# air.net
KiCad netlist of a schematic drawn in EAGLE
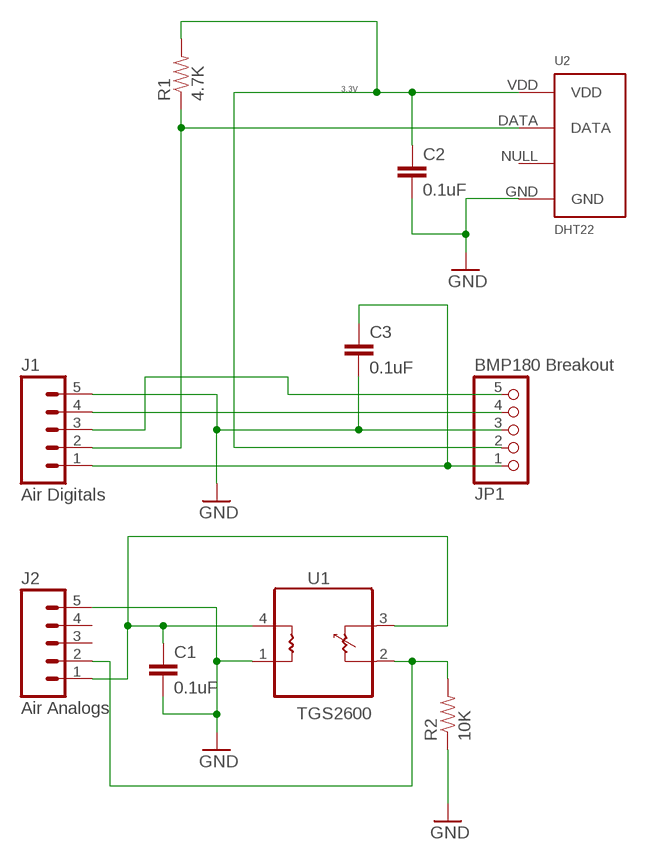
[diagram p0: schematic, sheet 1]

(export (version "E")
  (design (tool "Eeschema 10.0.6"))
  (components
    (comp (ref "C1")
      (value "0.1uF")
      (footprint "eagle-import:CAP-PTH-SMALL")
      (libsource (lib "eagle-import") (part "CAPPTH"))
    )
    (comp (ref "C2")
      (value "0.1uF")
      (footprint "eagle-import:CAP-PTH-SMALL")
      (libsource (lib "eagle-import") (part "CAPPTH"))
    )
    (comp (ref "C3")
      (value "0.1uF")
      (footprint "eagle-import:CAP-PTH-SMALL")
      (libsource (lib "eagle-import") (part "CAPPTH"))
    )
    (comp (ref "J1")
      (value "Air Digitals")
      (footprint "eagle-import:SCREWTERMINAL-3.5MM-5")
      (libsource (lib "eagle-import") (part "M05SCREW"))
    )
    (comp (ref "J2")
      (value "Air Analogs")
      (footprint "eagle-import:SCREWTERMINAL-3.5MM-5")
      (libsource (lib "eagle-import") (part "M05SCREW"))
    )
    (comp (ref "JP1")
      (value "BMP180 Breakout")
      (footprint "eagle-import:1X05_ROUND_70")
      (libsource (lib "eagle-import") (part "HEADER-1X570MIL"))
    )
    (comp (ref "R1")
      (value "4.7K")
      (footprint "eagle-import:AXIAL-0.4")
      (libsource (lib "eagle-import") (part "RESISTORPTH-1/4W"))
    )
    (comp (ref "R2")
      (value "10K")
      (footprint "eagle-import:AXIAL-0.4")
      (libsource (lib "eagle-import") (part "RESISTORPTH-1/4W"))
    )
    (comp (ref "U1")
      (value "TGS2600")
      (footprint "eagle-import:TO5_AIRQ")
      (libsource (lib "eagle-import") (part "TGN2600"))
    )
    (comp (ref "U2")
      (value "DHT22")
      (footprint "eagle-import:AM2302")
      (libsource (lib "eagle-import") (part "RHT03_DHT-22_AM2302WIRED"))
    )
  )
  (nets
    (net (code "1") (name "/3.3V") (class "Default")
      (node (ref "C2") (pin "1") (pinfunction "1_1") (pintype "passive"))
      (node (ref "JP1") (pin "2") (pinfunction "2_2") (pintype "passive"))
      (node (ref "R1") (pin "P$2") (pinfunction "2_P$2") (pintype "passive"))
      (node (ref "U2") (pin "VDD") (pinfunction "VDD_VDD") (pintype "power_in"))
    )
    (net (code "2") (name "GND") (class "Default")
      (node (ref "C1") (pin "2") (pinfunction "2_2") (pintype "passive"))
      (node (ref "C2") (pin "2") (pinfunction "2_2") (pintype "passive"))
      (node (ref "C3") (pin "2") (pinfunction "2_2") (pintype "passive"))
      (node (ref "J1") (pin "5") (pinfunction "5_5") (pintype "passive"))
      (node (ref "J2") (pin "5") (pinfunction "5_5") (pintype "passive"))
      (node (ref "JP1") (pin "3") (pinfunction "3_3") (pintype "passive"))
      (node (ref "R2") (pin "P$1") (pinfunction "1_P$1") (pintype "passive"))
      (node (ref "U1") (pin "1") (pinfunction "1_1") (pintype "passive"))
      (node (ref "U2") (pin "GND") (pinfunction "GND_GND") (pintype "power_in"))
    )
    (net (code "3") (name "Net-(C1-Pad1)") (class "Default")
      (node (ref "C1") (pin "1") (pinfunction "1_1") (pintype "passive"))
      (node (ref "J2") (pin "1") (pinfunction "1_1") (pintype "passive"))
      (node (ref "U1") (pin "3") (pinfunction "3_3") (pintype "passive"))
      (node (ref "U1") (pin "4") (pinfunction "4_4") (pintype "passive"))
    )
    (net (code "4") (name "Net-(C3-Pad1)") (class "Default")
      (node (ref "C3") (pin "1") (pinfunction "1_1") (pintype "passive"))
      (node (ref "J1") (pin "1") (pinfunction "1_1") (pintype "passive"))
      (node (ref "JP1") (pin "1") (pinfunction "1_1") (pintype "passive"))
    )
    (net (code "5") (name "Net-(J1-Pad3)") (class "Default")
      (node (ref "J1") (pin "3") (pinfunction "3_3") (pintype "passive"))
      (node (ref "JP1") (pin "5") (pinfunction "5_5") (pintype "passive"))
    )
    (net (code "6") (name "Net-(J1-Pad4)") (class "Default")
      (node (ref "J1") (pin "4") (pinfunction "4_4") (pintype "passive"))
      (node (ref "JP1") (pin "4") (pinfunction "4_4") (pintype "passive"))
    )
    (net (code "7") (name "Net-(R1-1)") (class "Default")
      (node (ref "J1") (pin "2") (pinfunction "2_2") (pintype "passive"))
      (node (ref "R1") (pin "P$1") (pinfunction "1_P$1") (pintype "passive"))
      (node (ref "U2") (pin "DATA") (pinfunction "DATA_DATA") (pintype "bidirectional"))
    )
    (net (code "8") (name "Net-(R2-2)") (class "Default")
      (node (ref "J2") (pin "2") (pinfunction "2_2") (pintype "passive"))
      (node (ref "R2") (pin "P$2") (pinfunction "2_P$2") (pintype "passive"))
      (node (ref "U1") (pin "2") (pinfunction "2_2") (pintype "passive"))
    )
    (net (code "9") (name "unconnected-(J2-Pad3)") (class "Default")
      (node (ref "J2") (pin "3") (pinfunction "3_3") (pintype "passive"))
    )
    (net (code "10") (name "unconnected-(J2-Pad4)") (class "Default")
      (node (ref "J2") (pin "4") (pinfunction "4_4") (pintype "passive"))
    )
    (net (code "11") (name "unconnected-(U2-PadNULL)") (class "Default")
      (node (ref "U2") (pin "NULL") (pinfunction "NULL_NULL") (pintype "no_connect"))
    )
  )
)
